# On_board_front_end.net
KiCad netlist of a schematic drawn in Altium Designer
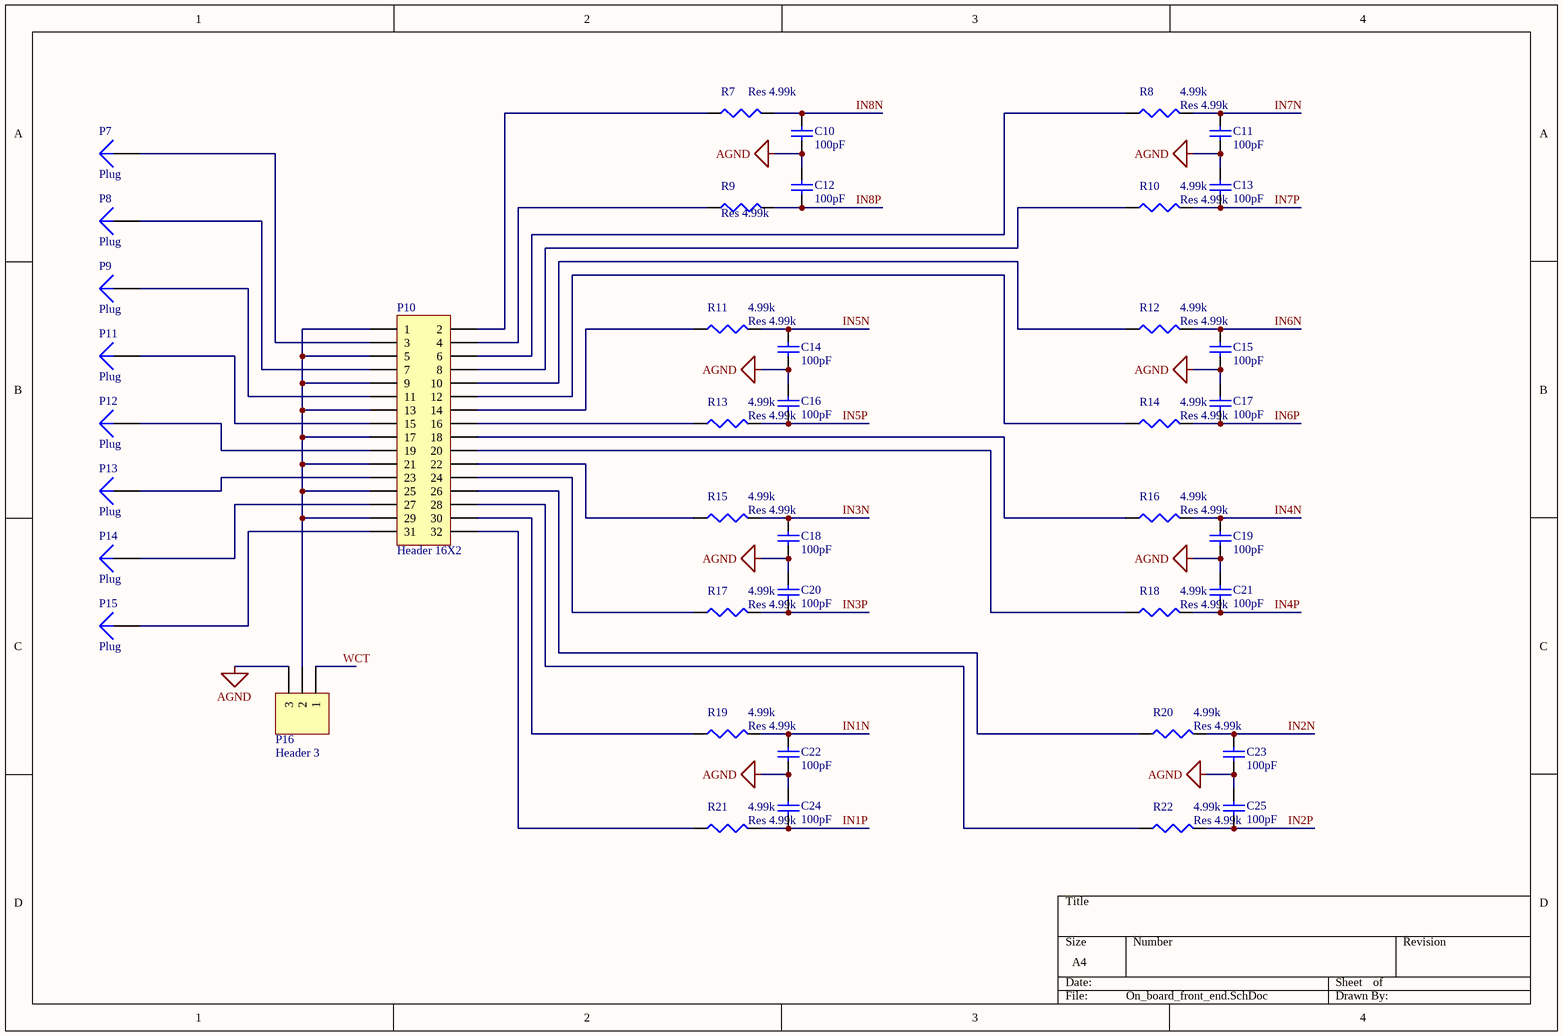
[diagram p0: On_board_front_end.SchDoc]

(export (version "E")
  (design (tool "Eeschema 10.0.6"))
  (components
    (comp (ref "C10")
      (value "100pF")
      (footprint "1608[0603]")
      (description "Capacitor")
      (fields (field (name "Comment") "Cap 100pF") (field (name "PUBLISHER") "Altium Limited"))
      (libsource (lib "Miscellaneous Devices") (part "Cap"))
    )
    (comp (ref "C11")
      (value "100pF")
      (footprint "1608[0603]")
      (description "Capacitor")
      (fields (field (name "Comment") "Cap 100pF") (field (name "PUBLISHER") "Altium Limited"))
      (libsource (lib "Miscellaneous Devices") (part "Cap"))
    )
    (comp (ref "C12")
      (value "100pF")
      (footprint "Miscellaneous Devices:1608[0603]")
      (description "Capacitor")
      (fields (field (name "Comment") "Cap 100pF") (field (name "PUBLISHER") "Altium Limited"))
      (libsource (lib "Miscellaneous Devices") (part "Cap"))
    )
    (comp (ref "C13")
      (value "100pF")
      (footprint "Miscellaneous Devices:1608[0603]")
      (description "Capacitor")
      (fields (field (name "Comment") "Cap 100pF") (field (name "PUBLISHER") "Altium Limited"))
      (libsource (lib "Miscellaneous Devices") (part "Cap"))
    )
    (comp (ref "C14")
      (value "100pF")
      (footprint "1608[0603]")
      (description "Capacitor")
      (fields (field (name "Comment") "Cap 100pF") (field (name "PUBLISHER") "Altium Limited"))
      (libsource (lib "Miscellaneous Devices") (part "Cap"))
    )
    (comp (ref "C15")
      (value "100pF")
      (footprint "1608[0603]")
      (description "Capacitor")
      (fields (field (name "Comment") "Cap 100pF") (field (name "PUBLISHER") "Altium Limited"))
      (libsource (lib "Miscellaneous Devices") (part "Cap"))
    )
    (comp (ref "C16")
      (value "100pF")
      (footprint "Miscellaneous Devices:1608[0603]")
      (description "Capacitor")
      (fields (field (name "Comment") "Cap 100pF") (field (name "PUBLISHER") "Altium Limited"))
      (libsource (lib "Miscellaneous Devices") (part "Cap"))
    )
    (comp (ref "C17")
      (value "100pF")
      (footprint "Miscellaneous Devices:1608[0603]")
      (description "Capacitor")
      (fields (field (name "Comment") "Cap 100pF") (field (name "PUBLISHER") "Altium Limited"))
      (libsource (lib "Miscellaneous Devices") (part "Cap"))
    )
    (comp (ref "C18")
      (value "100pF")
      (footprint "1608[0603]")
      (description "Capacitor")
      (fields (field (name "Comment") "Cap 100pF") (field (name "PUBLISHER") "Altium Limited"))
      (libsource (lib "Miscellaneous Devices") (part "Cap"))
    )
    (comp (ref "C19")
      (value "100pF")
      (footprint "1608[0603]")
      (description "Capacitor")
      (fields (field (name "Comment") "Cap 100pF") (field (name "PUBLISHER") "Altium Limited"))
      (libsource (lib "Miscellaneous Devices") (part "Cap"))
    )
    (comp (ref "C20")
      (value "100pF")
      (footprint "Miscellaneous Devices:1608[0603]")
      (description "Capacitor")
      (fields (field (name "Comment") "Cap 100pF") (field (name "PUBLISHER") "Altium Limited"))
      (libsource (lib "Miscellaneous Devices") (part "Cap"))
    )
    (comp (ref "C21")
      (value "100pF")
      (footprint "Miscellaneous Devices:1608[0603]")
      (description "Capacitor")
      (fields (field (name "Comment") "Cap 100pF") (field (name "PUBLISHER") "Altium Limited"))
      (libsource (lib "Miscellaneous Devices") (part "Cap"))
    )
    (comp (ref "C22")
      (value "100pF")
      (footprint "1608[0603]")
      (description "Capacitor")
      (fields (field (name "Comment") "Cap 100pF") (field (name "PUBLISHER") "Altium Limited"))
      (libsource (lib "Miscellaneous Devices") (part "Cap"))
    )
    (comp (ref "C23")
      (value "100pF")
      (footprint "1608[0603]")
      (description "Capacitor")
      (fields (field (name "Comment") "Cap 100pF") (field (name "PUBLISHER") "Altium Limited"))
      (libsource (lib "Miscellaneous Devices") (part "Cap"))
    )
    (comp (ref "C24")
      (value "100pF")
      (footprint "Miscellaneous Devices:1608[0603]")
      (description "Capacitor")
      (fields (field (name "Comment") "Cap 100pF") (field (name "PUBLISHER") "Altium Limited"))
      (libsource (lib "Miscellaneous Devices") (part "Cap"))
    )
    (comp (ref "C25")
      (value "100pF")
      (footprint "Miscellaneous Devices:1608[0603]")
      (description "Capacitor")
      (fields (field (name "Comment") "Cap 100pF") (field (name "PUBLISHER") "Altium Limited"))
      (libsource (lib "Miscellaneous Devices") (part "Cap"))
    )
    (comp (ref "P7")
      (value "Plug")
      (footprint "PIN1")
      (fields (field (name "PUBLISHER") "Altium Limited"))
      (libsource (lib "Miscellaneous Connectors") (part "Plug"))
    )
    (comp (ref "P8")
      (value "Plug")
      (footprint "PIN1")
      (fields (field (name "PUBLISHER") "Altium Limited"))
      (libsource (lib "Miscellaneous Connectors") (part "Plug"))
    )
    (comp (ref "P9")
      (value "Plug")
      (footprint "PIN1")
      (fields (field (name "PUBLISHER") "Altium Limited"))
      (libsource (lib "Miscellaneous Connectors") (part "Plug"))
    )
    (comp (ref "P10")
      (value "Header 16X2")
      (footprint "HDR2X16")
      (description "Header, 16-Pin, Dual row")
      (fields (field (name "PUBLISHER") "Altium Limited"))
      (libsource (lib "Miscellaneous Connectors") (part "Header 16X2"))
    )
    (comp (ref "P11")
      (value "Plug")
      (footprint "PIN1")
      (fields (field (name "PUBLISHER") "Altium Limited"))
      (libsource (lib "Miscellaneous Connectors") (part "Plug"))
    )
    (comp (ref "P12")
      (value "Plug")
      (footprint "PIN1")
      (fields (field (name "PUBLISHER") "Altium Limited"))
      (libsource (lib "Miscellaneous Connectors") (part "Plug"))
    )
    (comp (ref "P13")
      (value "Plug")
      (footprint "PIN1")
      (fields (field (name "PUBLISHER") "Altium Limited"))
      (libsource (lib "Miscellaneous Connectors") (part "Plug"))
    )
    (comp (ref "P14")
      (value "Plug")
      (footprint "PIN1")
      (fields (field (name "PUBLISHER") "Altium Limited"))
      (libsource (lib "Miscellaneous Connectors") (part "Plug"))
    )
    (comp (ref "P15")
      (value "Plug")
      (footprint "PIN1")
      (fields (field (name "PUBLISHER") "Altium Limited"))
      (libsource (lib "Miscellaneous Connectors") (part "Plug"))
    )
    (comp (ref "P16")
      (value "Header 3")
      (footprint "HDR1X3")
      (description "Header, 3-Pin")
      (fields (field (name "PUBLISHER") "Altium Limited"))
      (libsource (lib "Miscellaneous Connectors") (part "Header 3"))
    )
    (comp (ref "R7")
      (value "Res 4.99k")
      (footprint "0402")
      (description "Resistor")
      (fields (field (name "PUBLISHER") "Altium Limited"))
      (libsource (lib "Miscellaneous Devices") (part "Res3"))
    )
    (comp (ref "R8")
      (value "Res 4.99k")
      (footprint "0402")
      (description "Resistor")
      (fields (field (name "ALTIUM_VALUE") "4.99k") (field (name "PUBLISHER") "Altium Limited"))
      (libsource (lib "Miscellaneous Devices") (part "Res3"))
    )
    (comp (ref "R9")
      (value "Res 4.99k")
      (footprint "0402")
      (description "Resistor")
      (fields (field (name "PUBLISHER") "Altium Limited"))
      (libsource (lib "Miscellaneous Devices") (part "Res3"))
    )
    (comp (ref "R10")
      (value "Res 4.99k")
      (footprint "0402")
      (description "Resistor")
      (fields (field (name "ALTIUM_VALUE") "4.99k") (field (name "PUBLISHER") "Altium Limited"))
      (libsource (lib "Miscellaneous Devices") (part "Res3"))
    )
    (comp (ref "R11")
      (value "Res 4.99k")
      (footprint "0402")
      (description "Resistor")
      (fields (field (name "ALTIUM_VALUE") "4.99k") (field (name "PUBLISHER") "Altium Limited"))
      (libsource (lib "Miscellaneous Devices") (part "Res3"))
    )
    (comp (ref "R12")
      (value "Res 4.99k")
      (footprint "0402")
      (description "Resistor")
      (fields (field (name "ALTIUM_VALUE") "4.99k") (field (name "PUBLISHER") "Altium Limited"))
      (libsource (lib "Miscellaneous Devices") (part "Res3"))
    )
    (comp (ref "R13")
      (value "Res 4.99k")
      (footprint "0402")
      (description "Resistor")
      (fields (field (name "ALTIUM_VALUE") "4.99k") (field (name "PUBLISHER") "Altium Limited"))
      (libsource (lib "Miscellaneous Devices") (part "Res3"))
    )
    (comp (ref "R14")
      (value "Res 4.99k")
      (footprint "0402")
      (description "Resistor")
      (fields (field (name "ALTIUM_VALUE") "4.99k") (field (name "PUBLISHER") "Altium Limited"))
      (libsource (lib "Miscellaneous Devices") (part "Res3"))
    )
    (comp (ref "R15")
      (value "Res 4.99k")
      (footprint "0402")
      (description "Resistor")
      (fields (field (name "ALTIUM_VALUE") "4.99k") (field (name "PUBLISHER") "Altium Limited"))
      (libsource (lib "Miscellaneous Devices") (part "Res3"))
    )
    (comp (ref "R16")
      (value "Res 4.99k")
      (footprint "0402")
      (description "Resistor")
      (fields (field (name "ALTIUM_VALUE") "4.99k") (field (name "PUBLISHER") "Altium Limited"))
      (libsource (lib "Miscellaneous Devices") (part "Res3"))
    )
    (comp (ref "R17")
      (value "Res 4.99k")
      (footprint "0402")
      (description "Resistor")
      (fields (field (name "ALTIUM_VALUE") "4.99k") (field (name "PUBLISHER") "Altium Limited"))
      (libsource (lib "Miscellaneous Devices") (part "Res3"))
    )
    (comp (ref "R18")
      (value "Res 4.99k")
      (footprint "0402")
      (description "Resistor")
      (fields (field (name "ALTIUM_VALUE") "4.99k") (field (name "PUBLISHER") "Altium Limited"))
      (libsource (lib "Miscellaneous Devices") (part "Res3"))
    )
    (comp (ref "R19")
      (value "Res 4.99k")
      (footprint "0402")
      (description "Resistor")
      (fields (field (name "ALTIUM_VALUE") "4.99k") (field (name "PUBLISHER") "Altium Limited"))
      (libsource (lib "Miscellaneous Devices") (part "Res3"))
    )
    (comp (ref "R20")
      (value "Res 4.99k")
      (footprint "0402")
      (description "Resistor")
      (fields (field (name "ALTIUM_VALUE") "4.99k") (field (name "PUBLISHER") "Altium Limited"))
      (libsource (lib "Miscellaneous Devices") (part "Res3"))
    )
    (comp (ref "R21")
      (value "Res 4.99k")
      (footprint "0402")
      (description "Resistor")
      (fields (field (name "ALTIUM_VALUE") "4.99k") (field (name "PUBLISHER") "Altium Limited"))
      (libsource (lib "Miscellaneous Devices") (part "Res3"))
    )
    (comp (ref "R22")
      (value "Res 4.99k")
      (footprint "0402")
      (description "Resistor")
      (fields (field (name "ALTIUM_VALUE") "4.99k") (field (name "PUBLISHER") "Altium Limited"))
      (libsource (lib "Miscellaneous Devices") (part "Res3"))
    )
  )
  (nets
    (net (code "1") (name "/IN1N") (class "Default")
      (node (ref "C22") (pin "1") (pinfunction "1_1") (pintype "passive"))
      (node (ref "R19") (pin "2") (pinfunction "2_2") (pintype "passive"))
    )
    (net (code "2") (name "/IN1P") (class "Default")
      (node (ref "C24") (pin "2") (pinfunction "2_2") (pintype "passive"))
      (node (ref "R21") (pin "2") (pinfunction "2_2") (pintype "passive"))
    )
    (net (code "3") (name "/IN2N") (class "Default")
      (node (ref "C23") (pin "1") (pinfunction "1_1") (pintype "passive"))
      (node (ref "R20") (pin "2") (pinfunction "2_2") (pintype "passive"))
    )
    (net (code "4") (name "/IN2P") (class "Default")
      (node (ref "C25") (pin "2") (pinfunction "2_2") (pintype "passive"))
      (node (ref "R22") (pin "2") (pinfunction "2_2") (pintype "passive"))
    )
    (net (code "5") (name "/IN3N") (class "Default")
      (node (ref "C18") (pin "1") (pinfunction "1_1") (pintype "passive"))
      (node (ref "R15") (pin "2") (pinfunction "2_2") (pintype "passive"))
    )
    (net (code "6") (name "/IN3P") (class "Default")
      (node (ref "C20") (pin "2") (pinfunction "2_2") (pintype "passive"))
      (node (ref "R17") (pin "2") (pinfunction "2_2") (pintype "passive"))
    )
    (net (code "7") (name "/IN4N") (class "Default")
      (node (ref "C19") (pin "1") (pinfunction "1_1") (pintype "passive"))
      (node (ref "R16") (pin "2") (pinfunction "2_2") (pintype "passive"))
    )
    (net (code "8") (name "/IN4P") (class "Default")
      (node (ref "C21") (pin "2") (pinfunction "2_2") (pintype "passive"))
      (node (ref "R18") (pin "2") (pinfunction "2_2") (pintype "passive"))
    )
    (net (code "9") (name "/IN5N") (class "Default")
      (node (ref "C14") (pin "1") (pinfunction "1_1") (pintype "passive"))
      (node (ref "R11") (pin "2") (pinfunction "2_2") (pintype "passive"))
    )
    (net (code "10") (name "/IN5P") (class "Default")
      (node (ref "C16") (pin "2") (pinfunction "2_2") (pintype "passive"))
      (node (ref "R13") (pin "2") (pinfunction "2_2") (pintype "passive"))
    )
    (net (code "11") (name "/IN6N") (class "Default")
      (node (ref "C15") (pin "1") (pinfunction "1_1") (pintype "passive"))
      (node (ref "R12") (pin "2") (pinfunction "2_2") (pintype "passive"))
    )
    (net (code "12") (name "/IN6P") (class "Default")
      (node (ref "C17") (pin "2") (pinfunction "2_2") (pintype "passive"))
      (node (ref "R14") (pin "2") (pinfunction "2_2") (pintype "passive"))
    )
    (net (code "13") (name "/IN7N") (class "Default")
      (node (ref "C11") (pin "1") (pinfunction "1_1") (pintype "passive"))
      (node (ref "R8") (pin "2") (pinfunction "2_2") (pintype "passive"))
    )
    (net (code "14") (name "/IN7P") (class "Default")
      (node (ref "C13") (pin "2") (pinfunction "2_2") (pintype "passive"))
      (node (ref "R10") (pin "2") (pinfunction "2_2") (pintype "passive"))
    )
    (net (code "15") (name "/IN8N") (class "Default")
      (node (ref "C10") (pin "1") (pinfunction "1_1") (pintype "passive"))
      (node (ref "R7") (pin "2") (pinfunction "2_2") (pintype "passive"))
    )
    (net (code "16") (name "/IN8P") (class "Default")
      (node (ref "C12") (pin "2") (pinfunction "2_2") (pintype "passive"))
      (node (ref "R9") (pin "2") (pinfunction "2_2") (pintype "passive"))
    )
    (net (code "17") (name "/WCT") (class "Default")
      (node (ref "P16") (pin "1") (pinfunction "1_1") (pintype "passive"))
    )
    (net (code "18") (name "AGND") (class "Default")
      (node (ref "C10") (pin "2") (pinfunction "2_2") (pintype "passive"))
      (node (ref "C11") (pin "2") (pinfunction "2_2") (pintype "passive"))
      (node (ref "C12") (pin "1") (pinfunction "1_1") (pintype "passive"))
      (node (ref "C13") (pin "1") (pinfunction "1_1") (pintype "passive"))
      (node (ref "C14") (pin "2") (pinfunction "2_2") (pintype "passive"))
      (node (ref "C15") (pin "2") (pinfunction "2_2") (pintype "passive"))
      (node (ref "C16") (pin "1") (pinfunction "1_1") (pintype "passive"))
      (node (ref "C17") (pin "1") (pinfunction "1_1") (pintype "passive"))
      (node (ref "C18") (pin "2") (pinfunction "2_2") (pintype "passive"))
      (node (ref "C19") (pin "2") (pinfunction "2_2") (pintype "passive"))
      (node (ref "C20") (pin "1") (pinfunction "1_1") (pintype "passive"))
      (node (ref "C21") (pin "1") (pinfunction "1_1") (pintype "passive"))
      (node (ref "C22") (pin "2") (pinfunction "2_2") (pintype "passive"))
      (node (ref "C23") (pin "2") (pinfunction "2_2") (pintype "passive"))
      (node (ref "C24") (pin "1") (pinfunction "1_1") (pintype "passive"))
      (node (ref "C25") (pin "1") (pinfunction "1_1") (pintype "passive"))
      (node (ref "P16") (pin "3") (pinfunction "3_3") (pintype "passive"))
    )
    (net (code "19") (name "Net-(P10-Pad1)") (class "Default")
      (node (ref "P10") (pin "1") (pinfunction "1_1") (pintype "passive"))
      (node (ref "P10") (pin "13") (pinfunction "13_13") (pintype "passive"))
      (node (ref "P10") (pin "17") (pinfunction "17_17") (pintype "passive"))
      (node (ref "P10") (pin "21") (pinfunction "21_21") (pintype "passive"))
      (node (ref "P10") (pin "25") (pinfunction "25_25") (pintype "passive"))
      (node (ref "P10") (pin "29") (pinfunction "29_29") (pintype "passive"))
      (node (ref "P10") (pin "5") (pinfunction "5_5") (pintype "passive"))
      (node (ref "P10") (pin "9") (pinfunction "9_9") (pintype "passive"))
      (node (ref "P16") (pin "2") (pinfunction "2_2") (pintype "passive"))
    )
    (net (code "20") (name "Net-(P10-Pad2)") (class "Default")
      (node (ref "P10") (pin "2") (pinfunction "2_2") (pintype "passive"))
      (node (ref "R7") (pin "1") (pinfunction "1_1") (pintype "passive"))
    )
    (net (code "21") (name "Net-(P10-Pad3)") (class "Default")
      (node (ref "P10") (pin "3") (pinfunction "3_3") (pintype "passive"))
      (node (ref "P7") (pin "1") (pinfunction "1_1") (pintype "passive"))
    )
    (net (code "22") (name "Net-(P10-Pad4)") (class "Default")
      (node (ref "P10") (pin "4") (pinfunction "4_4") (pintype "passive"))
      (node (ref "R9") (pin "1") (pinfunction "1_1") (pintype "passive"))
    )
    (net (code "23") (name "Net-(P10-Pad6)") (class "Default")
      (node (ref "P10") (pin "6") (pinfunction "6_6") (pintype "passive"))
      (node (ref "R8") (pin "1") (pinfunction "1_1") (pintype "passive"))
    )
    (net (code "24") (name "Net-(P10-Pad7)") (class "Default")
      (node (ref "P10") (pin "7") (pinfunction "7_7") (pintype "passive"))
      (node (ref "P8") (pin "1") (pinfunction "1_1") (pintype "passive"))
    )
    (net (code "25") (name "Net-(P10-Pad8)") (class "Default")
      (node (ref "P10") (pin "8") (pinfunction "8_8") (pintype "passive"))
      (node (ref "R10") (pin "1") (pinfunction "1_1") (pintype "passive"))
    )
    (net (code "26") (name "Net-(P10-Pad10)") (class "Default")
      (node (ref "P10") (pin "10") (pinfunction "10_10") (pintype "passive"))
      (node (ref "R12") (pin "1") (pinfunction "1_1") (pintype "passive"))
    )
    (net (code "27") (name "Net-(P10-Pad11)") (class "Default")
      (node (ref "P10") (pin "11") (pinfunction "11_11") (pintype "passive"))
      (node (ref "P9") (pin "1") (pinfunction "1_1") (pintype "passive"))
    )
    (net (code "28") (name "Net-(P10-Pad12)") (class "Default")
      (node (ref "P10") (pin "12") (pinfunction "12_12") (pintype "passive"))
      (node (ref "R14") (pin "1") (pinfunction "1_1") (pintype "passive"))
    )
    (net (code "29") (name "Net-(P10-Pad14)") (class "Default")
      (node (ref "P10") (pin "14") (pinfunction "14_14") (pintype "passive"))
      (node (ref "R11") (pin "1") (pinfunction "1_1") (pintype "passive"))
    )
    (net (code "30") (name "Net-(P10-Pad15)") (class "Default")
      (node (ref "P10") (pin "15") (pinfunction "15_15") (pintype "passive"))
      (node (ref "P11") (pin "1") (pinfunction "1_1") (pintype "passive"))
    )
    (net (code "31") (name "Net-(P10-Pad16)") (class "Default")
      (node (ref "P10") (pin "16") (pinfunction "16_16") (pintype "passive"))
      (node (ref "R13") (pin "1") (pinfunction "1_1") (pintype "passive"))
    )
    (net (code "32") (name "Net-(P10-Pad18)") (class "Default")
      (node (ref "P10") (pin "18") (pinfunction "18_18") (pintype "passive"))
      (node (ref "R16") (pin "1") (pinfunction "1_1") (pintype "passive"))
    )
    (net (code "33") (name "Net-(P10-Pad19)") (class "Default")
      (node (ref "P10") (pin "19") (pinfunction "19_19") (pintype "passive"))
      (node (ref "P12") (pin "1") (pinfunction "1_1") (pintype "passive"))
    )
    (net (code "34") (name "Net-(P10-Pad20)") (class "Default")
      (node (ref "P10") (pin "20") (pinfunction "20_20") (pintype "passive"))
      (node (ref "R18") (pin "1") (pinfunction "1_1") (pintype "passive"))
    )
    (net (code "35") (name "Net-(P10-Pad22)") (class "Default")
      (node (ref "P10") (pin "22") (pinfunction "22_22") (pintype "passive"))
      (node (ref "R15") (pin "1") (pinfunction "1_1") (pintype "passive"))
    )
    (net (code "36") (name "Net-(P10-Pad23)") (class "Default")
      (node (ref "P10") (pin "23") (pinfunction "23_23") (pintype "passive"))
      (node (ref "P13") (pin "1") (pinfunction "1_1") (pintype "passive"))
    )
    (net (code "37") (name "Net-(P10-Pad24)") (class "Default")
      (node (ref "P10") (pin "24") (pinfunction "24_24") (pintype "passive"))
      (node (ref "R17") (pin "1") (pinfunction "1_1") (pintype "passive"))
    )
    (net (code "38") (name "Net-(P10-Pad26)") (class "Default")
      (node (ref "P10") (pin "26") (pinfunction "26_26") (pintype "passive"))
      (node (ref "R20") (pin "1") (pinfunction "1_1") (pintype "passive"))
    )
    (net (code "39") (name "Net-(P10-Pad27)") (class "Default")
      (node (ref "P10") (pin "27") (pinfunction "27_27") (pintype "passive"))
      (node (ref "P14") (pin "1") (pinfunction "1_1") (pintype "passive"))
    )
    (net (code "40") (name "Net-(P10-Pad28)") (class "Default")
      (node (ref "P10") (pin "28") (pinfunction "28_28") (pintype "passive"))
      (node (ref "R22") (pin "1") (pinfunction "1_1") (pintype "passive"))
    )
    (net (code "41") (name "Net-(P10-Pad30)") (class "Default")
      (node (ref "P10") (pin "30") (pinfunction "30_30") (pintype "passive"))
      (node (ref "R19") (pin "1") (pinfunction "1_1") (pintype "passive"))
    )
    (net (code "42") (name "Net-(P10-Pad31)") (class "Default")
      (node (ref "P10") (pin "31") (pinfunction "31_31") (pintype "passive"))
      (node (ref "P15") (pin "1") (pinfunction "1_1") (pintype "passive"))
    )
    (net (code "43") (name "Net-(P10-Pad32)") (class "Default")
      (node (ref "P10") (pin "32") (pinfunction "32_32") (pintype "passive"))
      (node (ref "R21") (pin "1") (pinfunction "1_1") (pintype "passive"))
    )
  )
)
